# akabeacon_square_type1.net
KiCad netlist of a schematic drawn in EAGLE
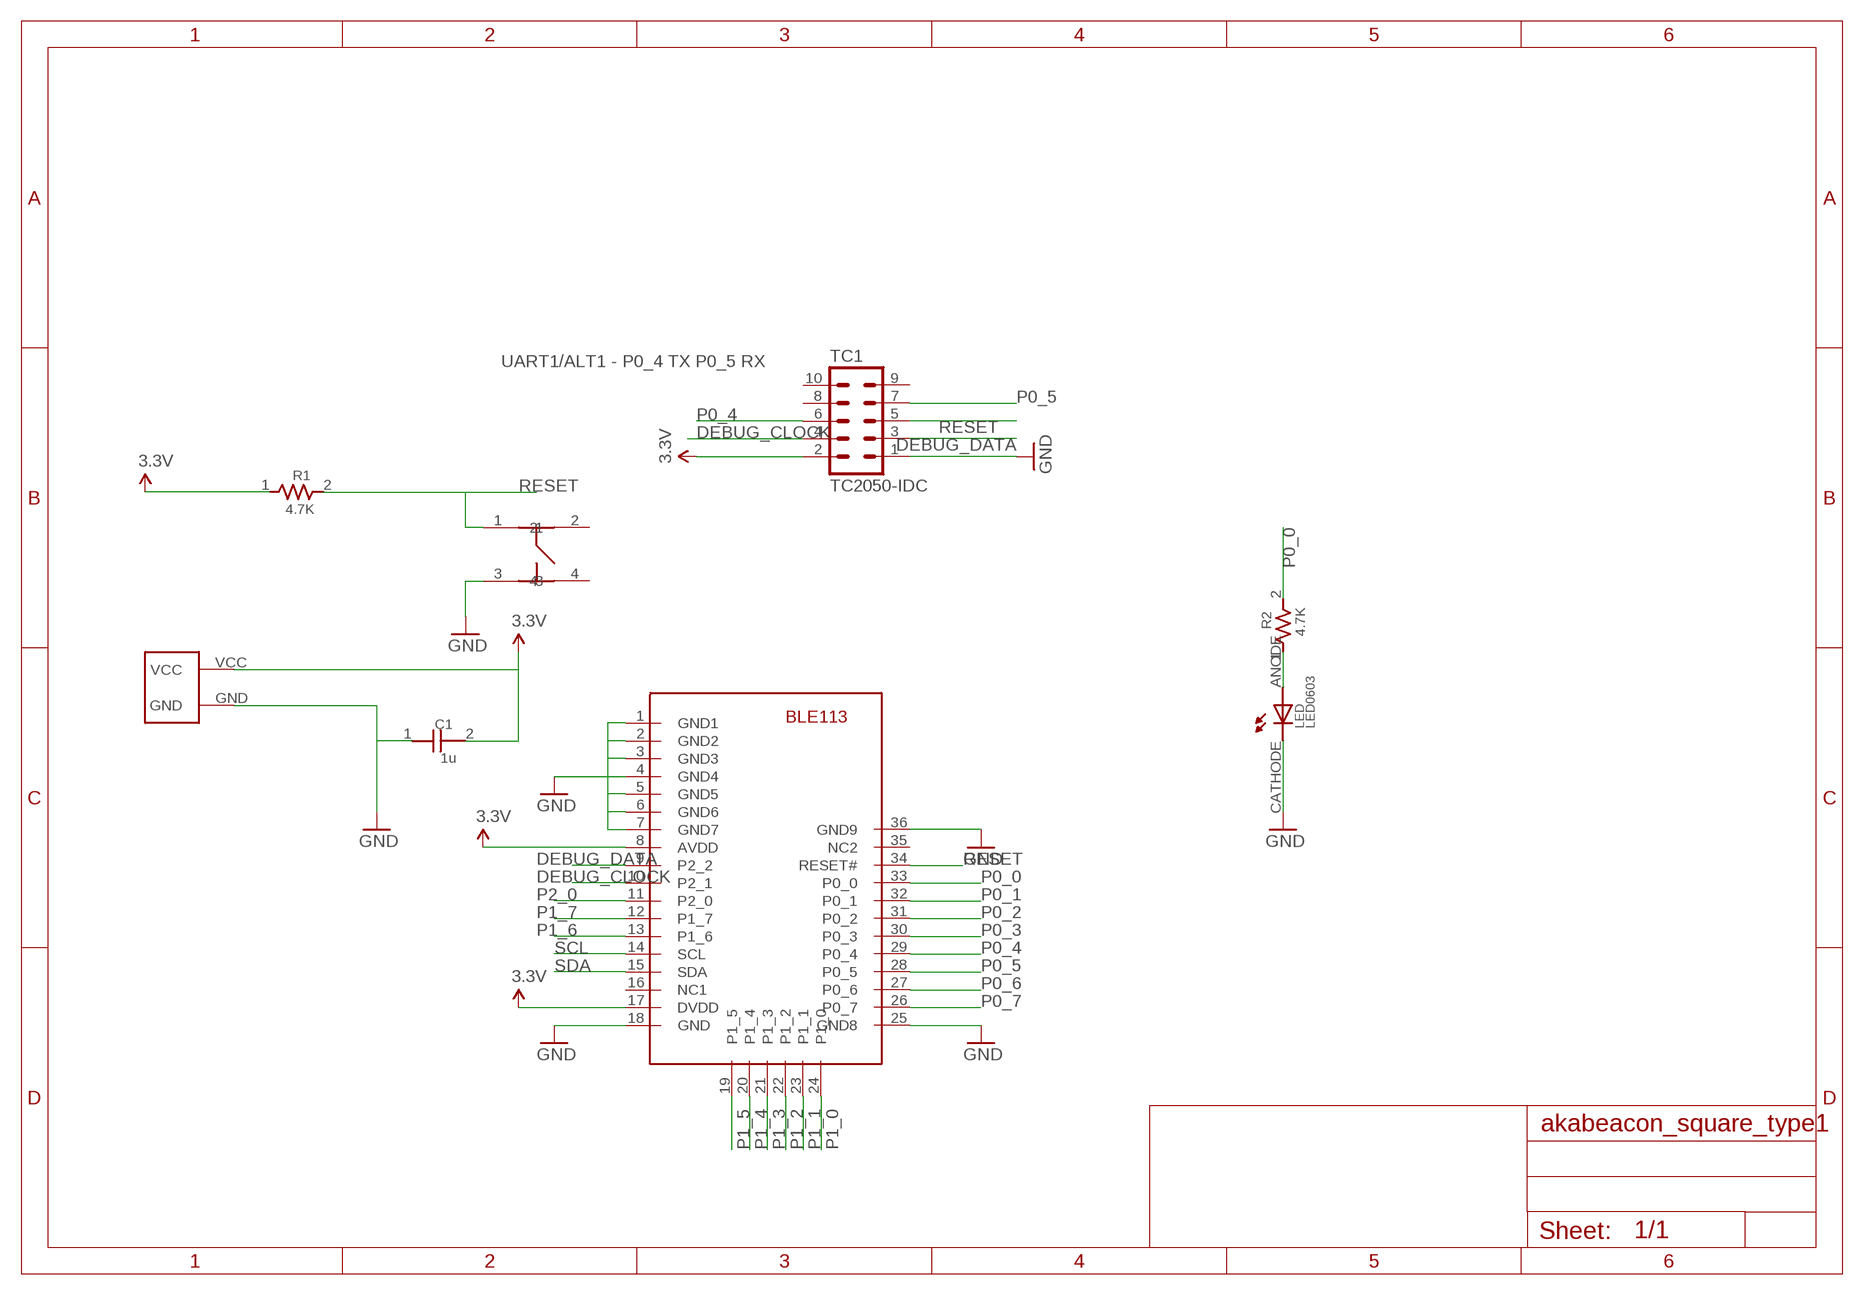
[diagram p0: schematic, sheet 1]

(export (version "E")
  (design (tool "Eeschema 10.0.6"))
  (components
    (comp (ref "C1")
      (value "1u")
      (footprint "eagle-import:0603")
      (libsource (lib "eagle-import") (part "CAPACITOR0603"))
    )
    (comp (ref "LED")
      (value "LED0603")
      (footprint "eagle-import:0603")
      (libsource (lib "eagle-import") (part "LED0603"))
    )
    (comp (ref "R1")
      (value "4.7K")
      (footprint "eagle-import:0603")
      (libsource (lib "eagle-import") (part "RESISTOR0603"))
    )
    (comp (ref "R2")
      (value "4.7K")
      (footprint "eagle-import:0603")
      (libsource (lib "eagle-import") (part "RESISTOR0603"))
    )
    (comp (ref "TC1")
      (value "TC2050-IDC")
      (footprint "eagle-import:TC2050-IDC-NL")
      (libsource (lib "eagle-import") (part "TC2050-IDC"))
    )
    (comp (ref "U$2")
      (value "SQUARE-TYPE1")
      (footprint "eagle-import:SQUARE-TYPE1-TC2030")
      (libsource (lib "eagle-import") (part "SQUARE-TYPE1"))
    )
    (comp (ref "U$5")
      (value "BLE113")
      (footprint "eagle-import:BLE113")
      (libsource (lib "eagle-import") (part "BLE113"))
    )
    (comp (ref "U$6")
      (value "SWICTH-4P(KMR2)")
      (footprint "eagle-import:SWITCH-4P(KMR2)")
      (libsource (lib "eagle-import") (part "SWICTH-4P(KMR2)"))
    )
  )
  (nets
    (net (code "1") (name "/DEBUG_CLOCK") (class "Default")
      (node (ref "TC1") (pin "4") (pinfunction "4_4") (pintype "passive"))
      (node (ref "U$5") (pin "10") (pinfunction "P2_1_10") (pintype "bidirectional"))
    )
    (net (code "2") (name "/DEBUG_DATA") (class "Default")
      (node (ref "TC1") (pin "3") (pinfunction "3_3") (pintype "passive"))
      (node (ref "U$5") (pin "9") (pinfunction "P2_2_9") (pintype "bidirectional"))
    )
    (net (code "3") (name "/P0_0") (class "Default")
      (node (ref "R2") (pin "2") (pinfunction "2_2") (pintype "passive"))
      (node (ref "U$5") (pin "33") (pinfunction "P0_0_33") (pintype "bidirectional"))
    )
    (net (code "4") (name "/P0_1") (class "Default")
      (node (ref "U$5") (pin "32") (pinfunction "P0_1_32") (pintype "bidirectional"))
    )
    (net (code "5") (name "/P0_2") (class "Default")
      (node (ref "U$5") (pin "31") (pinfunction "P0_2_31") (pintype "bidirectional"))
    )
    (net (code "6") (name "/P0_3") (class "Default")
      (node (ref "U$5") (pin "30") (pinfunction "P0_3_30") (pintype "bidirectional"))
    )
    (net (code "7") (name "/P0_4") (class "Default")
      (node (ref "TC1") (pin "6") (pinfunction "6_6") (pintype "passive"))
      (node (ref "U$5") (pin "29") (pinfunction "P0_4_29") (pintype "bidirectional"))
    )
    (net (code "8") (name "/P0_5") (class "Default")
      (node (ref "TC1") (pin "7") (pinfunction "7_7") (pintype "passive"))
      (node (ref "U$5") (pin "28") (pinfunction "P0_5_28") (pintype "bidirectional"))
    )
    (net (code "9") (name "/P0_6") (class "Default")
      (node (ref "U$5") (pin "27") (pinfunction "P0_6_27") (pintype "bidirectional"))
    )
    (net (code "10") (name "/P0_7") (class "Default")
      (node (ref "U$5") (pin "26") (pinfunction "P0_7_26") (pintype "bidirectional"))
    )
    (net (code "11") (name "/P1_0") (class "Default")
      (node (ref "U$5") (pin "24") (pinfunction "P1_0_24") (pintype "bidirectional"))
    )
    (net (code "12") (name "/P1_1") (class "Default")
      (node (ref "U$5") (pin "23") (pinfunction "P1_1_23") (pintype "bidirectional"))
    )
    (net (code "13") (name "/P1_2") (class "Default")
      (node (ref "U$5") (pin "22") (pinfunction "P1_2_22") (pintype "bidirectional"))
    )
    (net (code "14") (name "/P1_3") (class "Default")
      (node (ref "U$5") (pin "21") (pinfunction "P1_3_21") (pintype "bidirectional"))
    )
    (net (code "15") (name "/P1_4") (class "Default")
      (node (ref "U$5") (pin "20") (pinfunction "P1_4_20") (pintype "bidirectional"))
    )
    (net (code "16") (name "/P1_5") (class "Default")
      (node (ref "U$5") (pin "19") (pinfunction "P1_5_19") (pintype "bidirectional"))
    )
    (net (code "17") (name "/P1_6") (class "Default")
      (node (ref "U$5") (pin "13") (pinfunction "P1_6_13") (pintype "bidirectional"))
    )
    (net (code "18") (name "/P1_7") (class "Default")
      (node (ref "U$5") (pin "12") (pinfunction "P1_7_12") (pintype "bidirectional"))
    )
    (net (code "19") (name "/P2_0") (class "Default")
      (node (ref "U$5") (pin "11") (pinfunction "P2_0_11") (pintype "bidirectional"))
    )
    (net (code "20") (name "/RESET") (class "Default")
      (node (ref "R1") (pin "2") (pinfunction "2_2") (pintype "passive"))
      (node (ref "TC1") (pin "5") (pinfunction "5_5") (pintype "passive"))
      (node (ref "U$5") (pin "34") (pinfunction "RESET#_34") (pintype "bidirectional"))
      (node (ref "U$6") (pin "1") (pinfunction "1_1") (pintype "bidirectional"))
    )
    (net (code "21") (name "/SCL") (class "Default")
      (node (ref "U$5") (pin "14") (pinfunction "SCL_14") (pintype "bidirectional"))
    )
    (net (code "22") (name "/SDA") (class "Default")
      (node (ref "U$5") (pin "15") (pinfunction "SDA_15") (pintype "bidirectional"))
    )
    (net (code "23") (name "3.3V") (class "Default")
      (node (ref "C1") (pin "2") (pinfunction "2_2") (pintype "passive"))
      (node (ref "R1") (pin "1") (pinfunction "1_1") (pintype "passive"))
      (node (ref "TC1") (pin "2") (pinfunction "2_2") (pintype "passive"))
      (node (ref "U$2") (pin "VCC") (pinfunction "VCC_VCC") (pintype "bidirectional"))
      (node (ref "U$5") (pin "17") (pinfunction "DVDD_17") (pintype "bidirectional"))
      (node (ref "U$5") (pin "8") (pinfunction "AVDD_8") (pintype "bidirectional"))
    )
    (net (code "24") (name "GND") (class "Default")
      (node (ref "C1") (pin "1") (pinfunction "1_1") (pintype "passive"))
      (node (ref "LED") (pin "CATHODE") (pinfunction "CATHODE_CATHODE") (pintype "passive"))
      (node (ref "TC1") (pin "1") (pinfunction "1_1") (pintype "passive"))
      (node (ref "U$2") (pin "GND") (pinfunction "GND_GND") (pintype "bidirectional"))
      (node (ref "U$5") (pin "1") (pinfunction "GND1_1") (pintype "bidirectional"))
      (node (ref "U$5") (pin "18") (pinfunction "GND_18") (pintype "bidirectional"))
      (node (ref "U$5") (pin "2") (pinfunction "GND2_2") (pintype "bidirectional"))
      (node (ref "U$5") (pin "25") (pinfunction "GND8_25") (pintype "bidirectional"))
      (node (ref "U$5") (pin "3") (pinfunction "GND3_3") (pintype "bidirectional"))
      (node (ref "U$5") (pin "36") (pinfunction "GND9_36") (pintype "bidirectional"))
      (node (ref "U$5") (pin "4") (pinfunction "GND4_4") (pintype "bidirectional"))
      (node (ref "U$5") (pin "5") (pinfunction "GND5_5") (pintype "bidirectional"))
      (node (ref "U$5") (pin "6") (pinfunction "GND6_6") (pintype "bidirectional"))
      (node (ref "U$5") (pin "7") (pinfunction "GND7_7") (pintype "bidirectional"))
      (node (ref "U$6") (pin "3") (pinfunction "3_3") (pintype "bidirectional"))
    )
    (net (code "25") (name "Net-(LED-PadANODE)") (class "Default")
      (node (ref "LED") (pin "ANODE") (pinfunction "ANODE_ANODE") (pintype "passive"))
      (node (ref "R2") (pin "1") (pinfunction "1_1") (pintype "passive"))
    )
    (net (code "26") (name "unconnected-(TC1-Pad8)") (class "Default")
      (node (ref "TC1") (pin "8") (pinfunction "8_8") (pintype "passive"))
    )
    (net (code "27") (name "unconnected-(TC1-Pad9)") (class "Default")
      (node (ref "TC1") (pin "9") (pinfunction "9_9") (pintype "passive"))
    )
    (net (code "28") (name "unconnected-(TC1-Pad10)") (class "Default")
      (node (ref "TC1") (pin "10") (pinfunction "10_10") (pintype "passive"))
    )
    (net (code "29") (name "unconnected-(U$5-NC1-Pad16)") (class "Default")
      (node (ref "U$5") (pin "16") (pinfunction "NC1_16") (pintype "bidirectional"))
    )
    (net (code "30") (name "unconnected-(U$5-NC2-Pad35)") (class "Default")
      (node (ref "U$5") (pin "35") (pinfunction "NC2_35") (pintype "bidirectional"))
    )
    (net (code "31") (name "unconnected-(U$6-Pad2)") (class "Default")
      (node (ref "U$6") (pin "2") (pinfunction "2_2") (pintype "bidirectional"))
    )
    (net (code "32") (name "unconnected-(U$6-Pad4)") (class "Default")
      (node (ref "U$6") (pin "4") (pinfunction "4_4") (pintype "bidirectional"))
    )
  )
)
